# Sheet1.net
KiCad netlist of a schematic drawn in Altium Designer
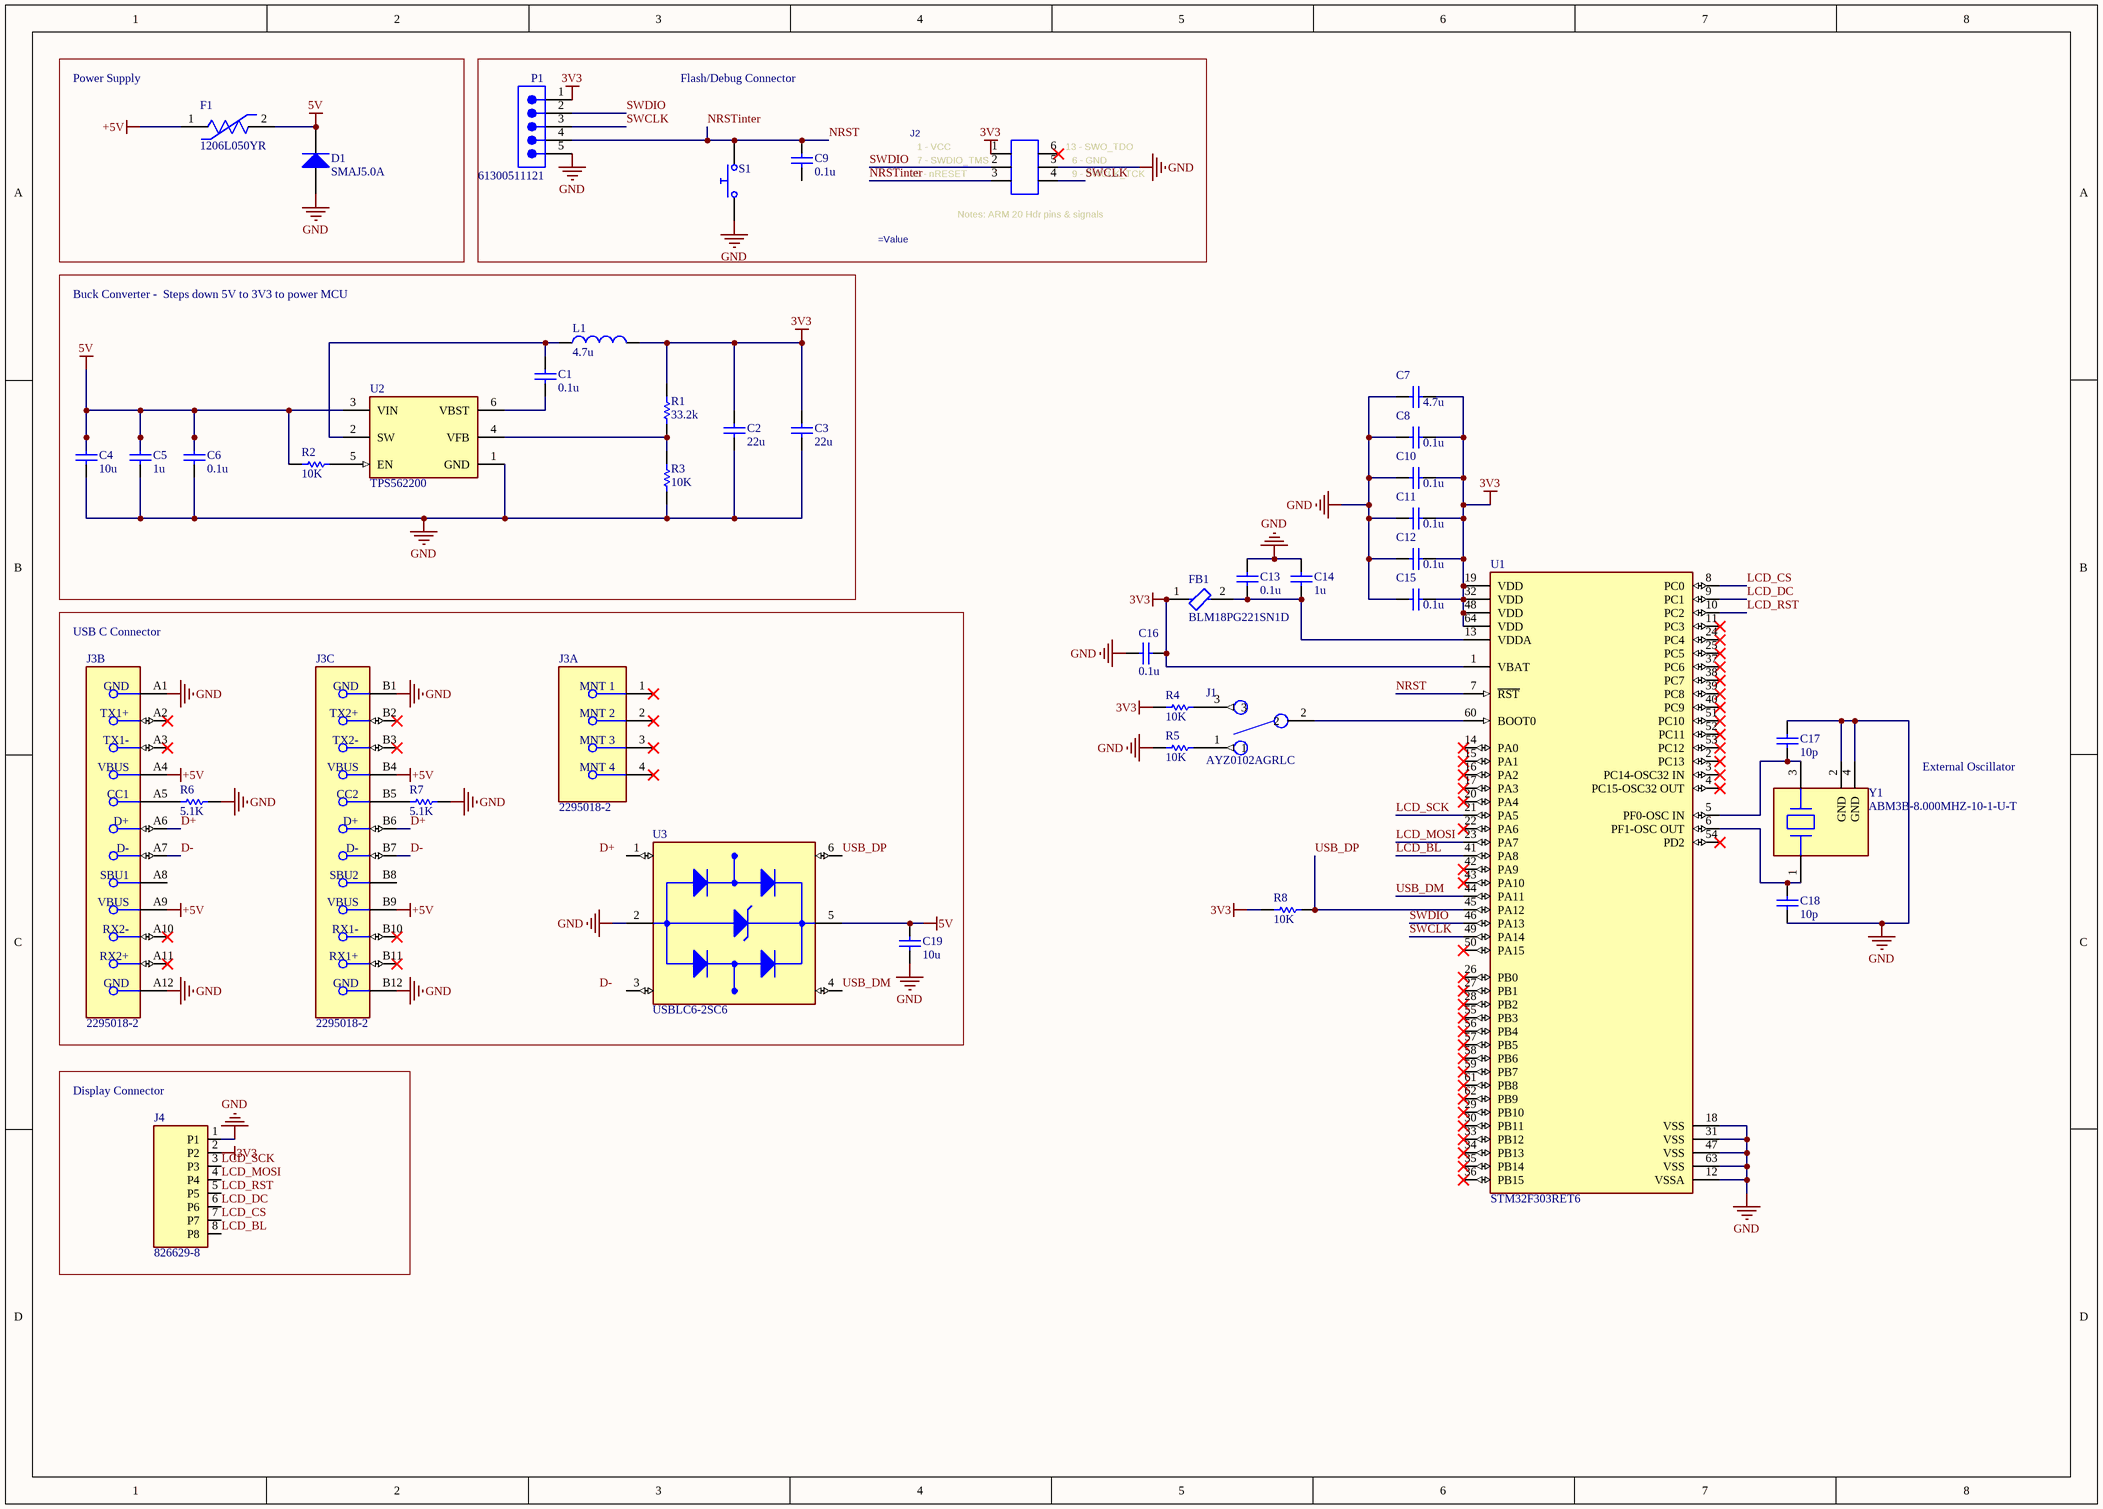
[diagram p0: Sheet1.SchDoc]

(export (version "E")
  (design (tool "Eeschema 10.0.6"))
  (components
    (comp (ref "C1")
      (value "0.1u")
      (description "Capacitor")
      (libsource (lib "Simulation Generic Components") (part "Capacitor"))
    )
    (comp (ref "C2")
      (value "22u")
      (description "Capacitor")
      (libsource (lib "Simulation Generic Components") (part "Capacitor"))
    )
    (comp (ref "C3")
      (value "22u")
      (description "Capacitor")
      (libsource (lib "Simulation Generic Components") (part "Capacitor"))
    )
    (comp (ref "C4")
      (value "10u")
      (description "Capacitor")
      (libsource (lib "Simulation Generic Components") (part "Capacitor"))
    )
    (comp (ref "C5")
      (value "1u")
      (description "Capacitor")
      (libsource (lib "Simulation Generic Components") (part "Capacitor"))
    )
    (comp (ref "C6")
      (value "0.1u")
      (description "Capacitor")
      (libsource (lib "Simulation Generic Components") (part "Capacitor"))
    )
    (comp (ref "C7")
      (value "4.7u")
      (description "Capacitor")
      (libsource (lib "Simulation Generic Components") (part "Capacitor"))
    )
    (comp (ref "C8")
      (value "0.1u")
      (description "Capacitor")
      (libsource (lib "Simulation Generic Components") (part "Capacitor"))
    )
    (comp (ref "C9")
      (value "0.1u")
      (description "Capacitor")
      (libsource (lib "Simulation Generic Components") (part "Capacitor"))
    )
    (comp (ref "C10")
      (value "0.1u")
      (description "Capacitor")
      (libsource (lib "Simulation Generic Components") (part "Capacitor"))
    )
    (comp (ref "C11")
      (value "0.1u")
      (description "Capacitor")
      (libsource (lib "Simulation Generic Components") (part "Capacitor"))
    )
    (comp (ref "C12")
      (value "0.1u")
      (description "Capacitor")
      (libsource (lib "Simulation Generic Components") (part "Capacitor"))
    )
    (comp (ref "C13")
      (value "0.1u")
      (description "Capacitor")
      (libsource (lib "Simulation Generic Components") (part "Capacitor"))
    )
    (comp (ref "C14")
      (value "1u")
      (description "Capacitor")
      (libsource (lib "Simulation Generic Components") (part "Capacitor"))
    )
    (comp (ref "C15")
      (value "0.1u")
      (description "Capacitor")
      (libsource (lib "Simulation Generic Components") (part "Capacitor"))
    )
    (comp (ref "C16")
      (value "0.1u")
      (description "Capacitor")
      (libsource (lib "Simulation Generic Components") (part "Capacitor"))
    )
    (comp (ref "C17")
      (value "10p")
      (description "Capacitor")
      (libsource (lib "Simulation Generic Components") (part "Capacitor"))
    )
    (comp (ref "C18")
      (value "10p")
      (description "Capacitor")
      (libsource (lib "Simulation Generic Components") (part "Capacitor"))
    )
    (comp (ref "C19")
      (value "10u")
      (description "Capacitor")
      (libsource (lib "Simulation Generic Components") (part "Capacitor"))
    )
    (comp (ref "D1")
      (value "SMAJ5.0A")
      (footprint "BOUR-SMA-2_V")
      (fields (field (name "MANUFACTURER") "Bourns"))
      (libsource (lib "Altium Content Vault") (part "D-AK-2"))
    )
    (comp (ref "F1")
      (value "1206L050YR")
      (footprint "FP-1206L050YR-MFG")
      (description "PTC RESET FUSE 6V 500MA 1206")
      (libsource (lib "Altium Content Vault") (part "fdf083d5f6389a9a1c4e51137f46658"))
    )
    (comp (ref "FB1")
      (value "BLM18PG221SN1D")
      (footprint "FP-BLM18-0_15-t0_8-IPC_B")
      (description "Chip Ferrite Bead, 0603, 220Ω @ 100MHz, 0.1Ω, 25%, 1.4A")
      (fields (field (name "TOLERANCE") "25%"))
      (libsource (lib "Altium Content Vault") (part "5f30dd21d616792df468990f7003faa"))
    )
    (comp (ref "J1")
      (value "AYZ0102AGRLC")
      (footprint "SW_AYZ0102AGRLC")
      (description "Slide Switch SPDT Surface Mount, Right Angle")
      (fields (field (name "MF") "C&K"))
      (libsource (lib "AYZ0102AGRLC") (part "AYZ0102AGRLC"))
    )
    (comp (ref "J2")
      (value "~")
      (footprint "TC2030-IDC")
      (description "HDR, TC2030, 6 Pin, Footprint only")
      (libsource (lib "TagConnect-20Apr2013") (part "HDR 6 TC2030-NL"))
    )
    (comp (ref "J3")
      (value "2295018-2")
      (footprint "FP-2295018-2-MFG")
      (description "CONN RCPT USB3.1 TYPEC 24POS SMD")
      (libsource (lib "Altium Content Vault") (part "679c62bc5b49f2b3fbc1f29b048fd31"))
    )
    (comp (ref "J4")
      (value "826629-8")
      (footprint "TE_826629-8")
      (description "Conn Unshrouded Header HDR 8 POS 2.54mm Solder ST Thru-Hole Automotive Box")
      (fields (field (name "MF") "TE Connectivity"))
      (libsource (lib "826629-8") (part "826629-8"))
    )
    (comp (ref "L1")
      (value "4.7u")
      (description "Inductor")
      (libsource (lib "Simulation Generic Components") (part "Inductor"))
    )
    (comp (ref "P1")
      (value "61300511121")
      (footprint "61300511121")
      (description "THT Vertical Pin Header WR-PHD, Pitch 2.54 mm, Single Row, 5 pins")
      (libsource (lib "Altium Content Vault") (part "Header_Male_1R_05P"))
    )
    (comp (ref "R1")
      (value "33.2k")
      (description "Resistor")
      (libsource (lib "Simulation Generic Components") (part "Resistor"))
    )
    (comp (ref "R2")
      (value "10K")
      (description "Resistor")
      (libsource (lib "Simulation Generic Components") (part "Resistor"))
    )
    (comp (ref "R3")
      (value "10K")
      (description "Resistor")
      (libsource (lib "Simulation Generic Components") (part "Resistor"))
    )
    (comp (ref "R4")
      (value "10K")
      (description "Resistor")
      (libsource (lib "Simulation Generic Components") (part "Resistor"))
    )
    (comp (ref "R5")
      (value "10K")
      (description "Resistor")
      (libsource (lib "Simulation Generic Components") (part "Resistor"))
    )
    (comp (ref "R6")
      (value "5.1K")
      (description "Resistor")
      (libsource (lib "Simulation Generic Components") (part "Resistor"))
    )
    (comp (ref "R7")
      (value "5.1K")
      (description "Resistor")
      (libsource (lib "Simulation Generic Components") (part "Resistor"))
    )
    (comp (ref "R8")
      (value "10K")
      (description "Resistor")
      (libsource (lib "Simulation Generic Components") (part "Resistor"))
    )
    (comp (ref "S1")
      (value "Push Button Normally Opened")
      (libsource (lib "Simulation Generic Components") (part "Push Button NO"))
    )
    (comp (ref "U1")
      (value "STM32F303RET6")
      (footprint "FP-LQFP64-5W-MFG")
      (description "IC MCU 32BIT 512KB FLASH 64LQFP")
      (fields
        (field (name "MANUFACTURER") "STMicroelectronics")
        (field (name "OCTOPART") "https://octopart.com/stm32f303ret6-stmicroelectronics-53115257")
      )
      (libsource (lib "Altium Content Vault") (part "7a78af9fccac3dafce8a4966595e415"))
    )
    (comp (ref "U2")
      (value "TPS562200")
      (footprint "FP-DDC0006A-MFG")
      (description "IC REG BUCK ADJ 2A TSOT23-6")
      (fields
        (field (name "MANUFACTURER PART NUMBER") "TPS562201DDCT")
        (field (name "OCTOPART") "https://octopart.com/tps562201ddct-texas+instruments-68059584")
      )
      (libsource (lib "Altium Content Vault") (part "06d79c7d29d628b4662ce6edb459819"))
    )
    (comp (ref "U3")
      (value "USBLC6-2SC6")
      (footprint "SOT95P280X145-6N")
      (description "17V Clamp 5A (8/20Âµs) Ipp Tvs Diode Surface Mount SOT-23-6")
      (fields (field (name "MF") "STMicroelectronics"))
      (libsource (lib "USBLC6-2SC6") (part "USBLC6-2SC6"))
    )
    (comp (ref "Y1")
      (value "ABM3B-8.000MHZ-10-1-U-T")
      (footprint "FP-ABM3B-MFG")
      (description "Crystal 8MHz ±10ppm 10pF SMD-4 5mm x 3.2mm")
      (libsource (lib "Altium Content Vault") (part "48e526d86b7f2615d98721063c72f49"))
    )
  )
  (nets
    (net (code "1") (name "+5V") (class "Default")
      (node (ref "F1") (pin "1") (pinfunction "1_1") (pintype "passive"))
      (node (ref "J3") (pin "A4") (pinfunction "VBUS_A4") (pintype "power_in"))
      (node (ref "J3") (pin "A9") (pinfunction "VBUS_A9") (pintype "power_in"))
      (node (ref "J3") (pin "B4") (pinfunction "VBUS_B4") (pintype "passive"))
      (node (ref "J3") (pin "B9") (pinfunction "VBUS_B9") (pintype "power_in"))
    )
    (net (code "2") (name "/D+") (class "Default")
      (node (ref "J3") (pin "A6") (pinfunction "D+_A6") (pintype "bidirectional"))
      (node (ref "J3") (pin "B6") (pinfunction "D+_B6") (pintype "bidirectional"))
    )
    (net (code "3") (name "/D-") (class "Default")
      (node (ref "J3") (pin "A7") (pinfunction "D-_A7") (pintype "bidirectional"))
      (node (ref "J3") (pin "B7") (pinfunction "D-_B7") (pintype "bidirectional"))
    )
    (net (code "4") (name "/LCD_BL") (class "Default")
      (node (ref "J4") (pin "8") (pinfunction "P8_8") (pintype "passive"))
      (node (ref "U1") (pin "41") (pinfunction "PA8_41") (pintype "bidirectional"))
    )
    (net (code "5") (name "/LCD_CS") (class "Default")
      (node (ref "J4") (pin "7") (pinfunction "P7_7") (pintype "passive"))
      (node (ref "U1") (pin "8") (pinfunction "PC0_8") (pintype "bidirectional"))
    )
    (net (code "6") (name "/LCD_DC") (class "Default")
      (node (ref "J4") (pin "6") (pinfunction "P6_6") (pintype "passive"))
      (node (ref "U1") (pin "9") (pinfunction "PC1_9") (pintype "bidirectional"))
    )
    (net (code "7") (name "/LCD_MOSI") (class "Default")
      (node (ref "J4") (pin "4") (pinfunction "P4_4") (pintype "passive"))
      (node (ref "U1") (pin "23") (pinfunction "PA7_23") (pintype "bidirectional"))
    )
    (net (code "8") (name "/LCD_RST") (class "Default")
      (node (ref "J4") (pin "5") (pinfunction "P5_5") (pintype "passive"))
      (node (ref "U1") (pin "10") (pinfunction "PC2_10") (pintype "bidirectional"))
    )
    (net (code "9") (name "/LCD_SCK") (class "Default")
      (node (ref "J4") (pin "3") (pinfunction "P3_3") (pintype "passive"))
      (node (ref "U1") (pin "21") (pinfunction "PA5_21") (pintype "bidirectional"))
    )
    (net (code "10") (name "/NRST") (class "Default")
      (node (ref "C9") (pin "2") (pinfunction "2_2") (pintype "passive"))
      (node (ref "J2") (pin "3") (pinfunction "3_3") (pintype "passive"))
      (node (ref "P1") (pin "4") (pinfunction "4_4") (pintype "passive"))
      (node (ref "S1") (pin "2") (pinfunction "2_2") (pintype "passive"))
      (node (ref "U1") (pin "7") (pinfunction "~{RST}_7") (pintype "input"))
    )
    (net (code "11") (name "/SWCLK") (class "Default")
      (node (ref "J2") (pin "4") (pinfunction "4_4") (pintype "passive"))
      (node (ref "P1") (pin "3") (pinfunction "3_3") (pintype "passive"))
      (node (ref "U1") (pin "49") (pinfunction "PA14_49") (pintype "bidirectional"))
    )
    (net (code "12") (name "/SWDIO") (class "Default")
      (node (ref "J2") (pin "2") (pinfunction "2_2") (pintype "passive"))
      (node (ref "P1") (pin "2") (pinfunction "2_2") (pintype "passive"))
      (node (ref "U1") (pin "46") (pinfunction "PA13_46") (pintype "bidirectional"))
    )
    (net (code "13") (name "/USB_DM") (class "Default")
      (node (ref "U1") (pin "44") (pinfunction "PA11_44") (pintype "bidirectional"))
      (node (ref "U3") (pin "4") (pinfunction "I/O2_OUT_4") (pintype "bidirectional"))
    )
    (net (code "14") (name "/USB_DP") (class "Default")
      (node (ref "R8") (pin "2") (pinfunction "2_2") (pintype "passive"))
      (node (ref "U1") (pin "45") (pinfunction "PA12_45") (pintype "bidirectional"))
      (node (ref "U3") (pin "6") (pinfunction "I/O1_OUT_6") (pintype "bidirectional"))
    )
    (net (code "15") (name "3V3") (class "Default")
      (node (ref "C10") (pin "1") (pinfunction "1_1") (pintype "passive"))
      (node (ref "C11") (pin "1") (pinfunction "1_1") (pintype "passive"))
      (node (ref "C12") (pin "1") (pinfunction "1_1") (pintype "passive"))
      (node (ref "C15") (pin "1") (pinfunction "1_1") (pintype "passive"))
      (node (ref "C16") (pin "2") (pinfunction "2_2") (pintype "passive"))
      (node (ref "C2") (pin "2") (pinfunction "2_2") (pintype "passive"))
      (node (ref "C3") (pin "2") (pinfunction "2_2") (pintype "passive"))
      (node (ref "C7") (pin "1") (pinfunction "1_1") (pintype "passive"))
      (node (ref "C8") (pin "1") (pinfunction "1_1") (pintype "passive"))
      (node (ref "FB1") (pin "1") (pinfunction "1_1") (pintype "passive"))
      (node (ref "J2") (pin "1") (pinfunction "1_1") (pintype "passive"))
      (node (ref "J4") (pin "2") (pinfunction "P2_2") (pintype "passive"))
      (node (ref "L1") (pin "2") (pinfunction "2_2") (pintype "passive"))
      (node (ref "P1") (pin "1") (pinfunction "1_1") (pintype "passive"))
      (node (ref "R1") (pin "1") (pinfunction "1_1") (pintype "passive"))
      (node (ref "R4") (pin "1") (pinfunction "1_1") (pintype "passive"))
      (node (ref "R8") (pin "1") (pinfunction "1_1") (pintype "passive"))
      (node (ref "U1") (pin "1") (pinfunction "VBAT_1") (pintype "power_in"))
      (node (ref "U1") (pin "19") (pinfunction "VDD_19") (pintype "power_in"))
      (node (ref "U1") (pin "32") (pinfunction "VDD_32") (pintype "power_in"))
      (node (ref "U1") (pin "48") (pinfunction "VDD_48") (pintype "power_in"))
      (node (ref "U1") (pin "64") (pinfunction "VDD_64") (pintype "power_in"))
    )
    (net (code "16") (name "5V") (class "Default")
      (node (ref "C19") (pin "2") (pinfunction "2_2") (pintype "passive"))
      (node (ref "C4") (pin "2") (pinfunction "2_2") (pintype "passive"))
      (node (ref "C5") (pin "2") (pinfunction "2_2") (pintype "passive"))
      (node (ref "C6") (pin "2") (pinfunction "2_2") (pintype "passive"))
      (node (ref "D1") (pin "2") (pinfunction "K_2") (pintype "passive"))
      (node (ref "F1") (pin "2") (pinfunction "2_2") (pintype "passive"))
      (node (ref "R2") (pin "2") (pinfunction "2_2") (pintype "passive"))
      (node (ref "U2") (pin "3") (pinfunction "VIN_3") (pintype "power_in"))
      (node (ref "U3") (pin "5") (pinfunction "VBUS_5") (pintype "power_in"))
    )
    (net (code "17") (name "GND") (class "Default")
      (node (ref "C10") (pin "2") (pinfunction "2_2") (pintype "passive"))
      (node (ref "C11") (pin "2") (pinfunction "2_2") (pintype "passive"))
      (node (ref "C12") (pin "2") (pinfunction "2_2") (pintype "passive"))
      (node (ref "C13") (pin "1") (pinfunction "1_1") (pintype "passive"))
      (node (ref "C14") (pin "2") (pinfunction "2_2") (pintype "passive"))
      (node (ref "C15") (pin "2") (pinfunction "2_2") (pintype "passive"))
      (node (ref "C16") (pin "1") (pinfunction "1_1") (pintype "passive"))
      (node (ref "C17") (pin "1") (pinfunction "1_1") (pintype "passive"))
      (node (ref "C18") (pin "2") (pinfunction "2_2") (pintype "passive"))
      (node (ref "C19") (pin "1") (pinfunction "1_1") (pintype "passive"))
      (node (ref "C2") (pin "1") (pinfunction "1_1") (pintype "passive"))
      (node (ref "C3") (pin "1") (pinfunction "1_1") (pintype "passive"))
      (node (ref "C4") (pin "1") (pinfunction "1_1") (pintype "passive"))
      (node (ref "C5") (pin "1") (pinfunction "1_1") (pintype "passive"))
      (node (ref "C6") (pin "1") (pinfunction "1_1") (pintype "passive"))
      (node (ref "C7") (pin "2") (pinfunction "2_2") (pintype "passive"))
      (node (ref "C8") (pin "2") (pinfunction "2_2") (pintype "passive"))
      (node (ref "D1") (pin "1") (pinfunction "A_1") (pintype "passive"))
      (node (ref "J2") (pin "5") (pinfunction "5_5") (pintype "passive"))
      (node (ref "J3") (pin "A1") (pinfunction "GND_A1") (pintype "power_in"))
      (node (ref "J3") (pin "A12") (pinfunction "GND_A12") (pintype "power_in"))
      (node (ref "J3") (pin "B1") (pinfunction "GND_B1") (pintype "power_in"))
      (node (ref "J3") (pin "B12") (pinfunction "GND_B12") (pintype "power_in"))
      (node (ref "J4") (pin "1") (pinfunction "P1_1") (pintype "passive"))
      (node (ref "P1") (pin "5") (pinfunction "5_5") (pintype "passive"))
      (node (ref "R3") (pin "2") (pinfunction "2_2") (pintype "passive"))
      (node (ref "R5") (pin "1") (pinfunction "1_1") (pintype "passive"))
      (node (ref "R6") (pin "1") (pinfunction "1_1") (pintype "passive"))
      (node (ref "R7") (pin "1") (pinfunction "1_1") (pintype "passive"))
      (node (ref "S1") (pin "1") (pinfunction "1_1") (pintype "passive"))
      (node (ref "U1") (pin "12") (pinfunction "VSSA_12") (pintype "power_in"))
      (node (ref "U1") (pin "18") (pinfunction "VSS_18") (pintype "power_in"))
      (node (ref "U1") (pin "31") (pinfunction "VSS_31") (pintype "power_in"))
      (node (ref "U1") (pin "47") (pinfunction "VSS_47") (pintype "power_in"))
      (node (ref "U1") (pin "63") (pinfunction "VSS_63") (pintype "power_in"))
      (node (ref "U2") (pin "1") (pinfunction "GND_1") (pintype "power_in"))
      (node (ref "U3") (pin "2") (pinfunction "GND_2") (pintype "power_in"))
      (node (ref "Y1") (pin "2") (pinfunction "GND_2") (pintype "power_in"))
      (node (ref "Y1") (pin "4") (pinfunction "GND_4") (pintype "power_in"))
    )
    (net (code "18") (name "Net-(J1-Pad1)") (class "Default")
      (node (ref "J1") (pin "1") (pinfunction "1_1") (pintype "output"))
      (node (ref "R5") (pin "2") (pinfunction "2_2") (pintype "passive"))
    )
    (net (code "19") (name "Net-(J1-Pad3)") (class "Default")
      (node (ref "J1") (pin "3") (pinfunction "3_3") (pintype "output"))
      (node (ref "R4") (pin "2") (pinfunction "2_2") (pintype "passive"))
    )
    (net (code "20") (name "Net-(J3B-CC1)") (class "Default")
      (node (ref "J3") (pin "A5") (pinfunction "CC1_A5") (pintype "passive"))
      (node (ref "R6") (pin "2") (pinfunction "2_2") (pintype "passive"))
    )
    (net (code "21") (name "Net-(J3C-CC2)") (class "Default")
      (node (ref "J3") (pin "B5") (pinfunction "CC2_B5") (pintype "passive"))
      (node (ref "R7") (pin "2") (pinfunction "2_2") (pintype "passive"))
    )
    (net (code "22") (name "Net-(U1-BOOT0)") (class "Default")
      (node (ref "J1") (pin "2") (pinfunction "2_2") (pintype "power_in"))
      (node (ref "U1") (pin "60") (pinfunction "BOOT0_60") (pintype "input"))
    )
    (net (code "23") (name "Net-(U1-PF0-OSC_IN)") (class "Default")
      (node (ref "C17") (pin "2") (pinfunction "2_2") (pintype "passive"))
      (node (ref "U1") (pin "5") (pinfunction "PF0-OSC_IN_5") (pintype "bidirectional"))
      (node (ref "Y1") (pin "3") (pinfunction "3_3") (pintype "passive"))
    )
    (net (code "24") (name "Net-(U1-PF1-OSC_OUT)") (class "Default")
      (node (ref "C18") (pin "1") (pinfunction "1_1") (pintype "passive"))
      (node (ref "U1") (pin "6") (pinfunction "PF1-OSC_OUT_6") (pintype "bidirectional"))
      (node (ref "Y1") (pin "1") (pinfunction "1_1") (pintype "passive"))
    )
    (net (code "25") (name "Net-(U1-VDDA)") (class "Default")
      (node (ref "C13") (pin "2") (pinfunction "2_2") (pintype "passive"))
      (node (ref "C14") (pin "1") (pinfunction "1_1") (pintype "passive"))
      (node (ref "FB1") (pin "2") (pinfunction "2_2") (pintype "passive"))
      (node (ref "U1") (pin "13") (pinfunction "VDDA_13") (pintype "power_in"))
    )
    (net (code "26") (name "Net-(U2-EN)") (class "Default")
      (node (ref "R2") (pin "1") (pinfunction "1_1") (pintype "passive"))
      (node (ref "U2") (pin "5") (pinfunction "EN_5") (pintype "input"))
    )
    (net (code "27") (name "Net-(U2-SW)") (class "Default")
      (node (ref "C1") (pin "2") (pinfunction "2_2") (pintype "passive"))
      (node (ref "L1") (pin "1") (pinfunction "1_1") (pintype "passive"))
      (node (ref "U2") (pin "2") (pinfunction "SW_2") (pintype "passive"))
    )
    (net (code "28") (name "Net-(U2-VBST)") (class "Default")
      (node (ref "C1") (pin "1") (pinfunction "1_1") (pintype "passive"))
      (node (ref "U2") (pin "6") (pinfunction "VBST_6") (pintype "power_in"))
    )
    (net (code "29") (name "Net-(U2-VFB)") (class "Default")
      (node (ref "R1") (pin "2") (pinfunction "2_2") (pintype "passive"))
      (node (ref "R3") (pin "1") (pinfunction "1_1") (pintype "passive"))
      (node (ref "U2") (pin "4") (pinfunction "VFB_4") (pintype "passive"))
    )
    (net (code "30") (name "unconnected-(C9-Pad1)") (class "Default")
      (node (ref "C9") (pin "1") (pinfunction "1_1") (pintype "passive"))
    )
    (net (code "31") (name "unconnected-(J2-Pad6)") (class "Default")
      (node (ref "J2") (pin "6") (pinfunction "6_6") (pintype "passive+no_connect"))
    )
    (net (code "32") (name "unconnected-(J3A-MNT_1-Pad1)") (class "Default")
      (node (ref "J3") (pin "1") (pinfunction "MNT_1_1") (pintype "passive+no_connect"))
    )
    (net (code "33") (name "unconnected-(J3A-MNT_2-Pad2)") (class "Default")
      (node (ref "J3") (pin "2") (pinfunction "MNT_2_2") (pintype "passive+no_connect"))
    )
    (net (code "34") (name "unconnected-(J3A-MNT_3-Pad3)") (class "Default")
      (node (ref "J3") (pin "3") (pinfunction "MNT_3_3") (pintype "passive+no_connect"))
    )
    (net (code "35") (name "unconnected-(J3A-MNT_4-Pad4)") (class "Default")
      (node (ref "J3") (pin "4") (pinfunction "MNT_4_4") (pintype "passive+no_connect"))
    )
    (net (code "36") (name "unconnected-(J3B-RX2+-PadA11)") (class "Default")
      (node (ref "J3") (pin "A11") (pinfunction "RX2+_A11") (pintype "bidirectional+no_connect"))
    )
    (net (code "37") (name "unconnected-(J3B-RX2--PadA10)") (class "Default")
      (node (ref "J3") (pin "A10") (pinfunction "RX2-_A10") (pintype "bidirectional+no_connect"))
    )
    (net (code "38") (name "unconnected-(J3B-SBU1-PadA8)") (class "Default")
      (node (ref "J3") (pin "A8") (pinfunction "SBU1_A8") (pintype "power_in"))
    )
    (net (code "39") (name "unconnected-(J3B-TX1+-PadA2)") (class "Default")
      (node (ref "J3") (pin "A2") (pinfunction "TX1+_A2") (pintype "bidirectional+no_connect"))
    )
    (net (code "40") (name "unconnected-(J3B-TX1--PadA3)") (class "Default")
      (node (ref "J3") (pin "A3") (pinfunction "TX1-_A3") (pintype "bidirectional+no_connect"))
    )
    (net (code "41") (name "unconnected-(J3C-RX1+-PadB11)") (class "Default")
      (node (ref "J3") (pin "B11") (pinfunction "RX1+_B11") (pintype "bidirectional+no_connect"))
    )
    (net (code "42") (name "unconnected-(J3C-RX1--PadB10)") (class "Default")
      (node (ref "J3") (pin "B10") (pinfunction "RX1-_B10") (pintype "bidirectional+no_connect"))
    )
    (net (code "43") (name "unconnected-(J3C-SBU2-PadB8)") (class "Default")
      (node (ref "J3") (pin "B8") (pinfunction "SBU2_B8") (pintype "passive"))
    )
    (net (code "44") (name "unconnected-(J3C-TX2+-PadB2)") (class "Default")
      (node (ref "J3") (pin "B2") (pinfunction "TX2+_B2") (pintype "bidirectional+no_connect"))
    )
    (net (code "45") (name "unconnected-(J3C-TX2--PadB3)") (class "Default")
      (node (ref "J3") (pin "B3") (pinfunction "TX2-_B3") (pintype "bidirectional+no_connect"))
    )
    (net (code "46") (name "unconnected-(U1-PA0-Pad14)") (class "Default")
      (node (ref "U1") (pin "14") (pinfunction "PA0_14") (pintype "bidirectional+no_connect"))
    )
    (net (code "47") (name "unconnected-(U1-PA1-Pad15)") (class "Default")
      (node (ref "U1") (pin "15") (pinfunction "PA1_15") (pintype "bidirectional+no_connect"))
    )
    (net (code "48") (name "unconnected-(U1-PA2-Pad16)") (class "Default")
      (node (ref "U1") (pin "16") (pinfunction "PA2_16") (pintype "bidirectional+no_connect"))
    )
    (net (code "49") (name "unconnected-(U1-PA3-Pad17)") (class "Default")
      (node (ref "U1") (pin "17") (pinfunction "PA3_17") (pintype "bidirectional+no_connect"))
    )
    (net (code "50") (name "unconnected-(U1-PA4-Pad20)") (class "Default")
      (node (ref "U1") (pin "20") (pinfunction "PA4_20") (pintype "bidirectional+no_connect"))
    )
    (net (code "51") (name "unconnected-(U1-PA6-Pad22)") (class "Default")
      (node (ref "U1") (pin "22") (pinfunction "PA6_22") (pintype "bidirectional+no_connect"))
    )
    (net (code "52") (name "unconnected-(U1-PA9-Pad42)") (class "Default")
      (node (ref "U1") (pin "42") (pinfunction "PA9_42") (pintype "bidirectional+no_connect"))
    )
    (net (code "53") (name "unconnected-(U1-PA10-Pad43)") (class "Default")
      (node (ref "U1") (pin "43") (pinfunction "PA10_43") (pintype "bidirectional+no_connect"))
    )
    (net (code "54") (name "unconnected-(U1-PA15-Pad50)") (class "Default")
      (node (ref "U1") (pin "50") (pinfunction "PA15_50") (pintype "bidirectional+no_connect"))
    )
    (net (code "55") (name "unconnected-(U1-PB0-Pad26)") (class "Default")
      (node (ref "U1") (pin "26") (pinfunction "PB0_26") (pintype "bidirectional+no_connect"))
    )
    (net (code "56") (name "unconnected-(U1-PB1-Pad27)") (class "Default")
      (node (ref "U1") (pin "27") (pinfunction "PB1_27") (pintype "bidirectional+no_connect"))
    )
    (net (code "57") (name "unconnected-(U1-PB2-Pad28)") (class "Default")
      (node (ref "U1") (pin "28") (pinfunction "PB2_28") (pintype "bidirectional+no_connect"))
    )
    (net (code "58") (name "unconnected-(U1-PB3-Pad55)") (class "Default")
      (node (ref "U1") (pin "55") (pinfunction "PB3_55") (pintype "bidirectional+no_connect"))
    )
    (net (code "59") (name "unconnected-(U1-PB4-Pad56)") (class "Default")
      (node (ref "U1") (pin "56") (pinfunction "PB4_56") (pintype "bidirectional+no_connect"))
    )
    (net (code "60") (name "unconnected-(U1-PB5-Pad57)") (class "Default")
      (node (ref "U1") (pin "57") (pinfunction "PB5_57") (pintype "bidirectional+no_connect"))
    )
    (net (code "61") (name "unconnected-(U1-PB6-Pad58)") (class "Default")
      (node (ref "U1") (pin "58") (pinfunction "PB6_58") (pintype "bidirectional+no_connect"))
    )
    (net (code "62") (name "unconnected-(U1-PB7-Pad59)") (class "Default")
      (node (ref "U1") (pin "59") (pinfunction "PB7_59") (pintype "bidirectional+no_connect"))
    )
    (net (code "63") (name "unconnected-(U1-PB8-Pad61)") (class "Default")
      (node (ref "U1") (pin "61") (pinfunction "PB8_61") (pintype "bidirectional+no_connect"))
    )
    (net (code "64") (name "unconnected-(U1-PB9-Pad62)") (class "Default")
      (node (ref "U1") (pin "62") (pinfunction "PB9_62") (pintype "bidirectional+no_connect"))
    )
    (net (code "65") (name "unconnected-(U1-PB10-Pad29)") (class "Default")
      (node (ref "U1") (pin "29") (pinfunction "PB10_29") (pintype "bidirectional+no_connect"))
    )
    (net (code "66") (name "unconnected-(U1-PB11-Pad30)") (class "Default")
      (node (ref "U1") (pin "30") (pinfunction "PB11_30") (pintype "bidirectional+no_connect"))
    )
    (net (code "67") (name "unconnected-(U1-PB12-Pad33)") (class "Default")
      (node (ref "U1") (pin "33") (pinfunction "PB12_33") (pintype "bidirectional+no_connect"))
    )
    (net (code "68") (name "unconnected-(U1-PB13-Pad34)") (class "Default")
      (node (ref "U1") (pin "34") (pinfunction "PB13_34") (pintype "bidirectional+no_connect"))
    )
    (net (code "69") (name "unconnected-(U1-PB14-Pad35)") (class "Default")
      (node (ref "U1") (pin "35") (pinfunction "PB14_35") (pintype "bidirectional+no_connect"))
    )
    (net (code "70") (name "unconnected-(U1-PB15-Pad36)") (class "Default")
      (node (ref "U1") (pin "36") (pinfunction "PB15_36") (pintype "bidirectional+no_connect"))
    )
    (net (code "71") (name "unconnected-(U1-PC3-Pad11)") (class "Default")
      (node (ref "U1") (pin "11") (pinfunction "PC3_11") (pintype "bidirectional+no_connect"))
    )
    (net (code "72") (name "unconnected-(U1-PC4-Pad24)") (class "Default")
      (node (ref "U1") (pin "24") (pinfunction "PC4_24") (pintype "bidirectional+no_connect"))
    )
    (net (code "73") (name "unconnected-(U1-PC5-Pad25)") (class "Default")
      (node (ref "U1") (pin "25") (pinfunction "PC5_25") (pintype "bidirectional+no_connect"))
    )
    (net (code "74") (name "unconnected-(U1-PC6-Pad37)") (class "Default")
      (node (ref "U1") (pin "37") (pinfunction "PC6_37") (pintype "bidirectional+no_connect"))
    )
    (net (code "75") (name "unconnected-(U1-PC7-Pad38)") (class "Default")
      (node (ref "U1") (pin "38") (pinfunction "PC7_38") (pintype "bidirectional+no_connect"))
    )
    (net (code "76") (name "unconnected-(U1-PC8-Pad39)") (class "Default")
      (node (ref "U1") (pin "39") (pinfunction "PC8_39") (pintype "bidirectional+no_connect"))
    )
    (net (code "77") (name "unconnected-(U1-PC9-Pad40)") (class "Default")
      (node (ref "U1") (pin "40") (pinfunction "PC9_40") (pintype "bidirectional+no_connect"))
    )
    (net (code "78") (name "unconnected-(U1-PC10-Pad51)") (class "Default")
      (node (ref "U1") (pin "51") (pinfunction "PC10_51") (pintype "bidirectional+no_connect"))
    )
    (net (code "79") (name "unconnected-(U1-PC11-Pad52)") (class "Default")
      (node (ref "U1") (pin "52") (pinfunction "PC11_52") (pintype "bidirectional+no_connect"))
    )
    (net (code "80") (name "unconnected-(U1-PC12-Pad53)") (class "Default")
      (node (ref "U1") (pin "53") (pinfunction "PC12_53") (pintype "bidirectional+no_connect"))
    )
    (net (code "81") (name "unconnected-(U1-PC13-Pad2)") (class "Default")
      (node (ref "U1") (pin "2") (pinfunction "PC13_2") (pintype "bidirectional+no_connect"))
    )
    (net (code "82") (name "unconnected-(U1-PC14-OSC32_IN-Pad3)") (class "Default")
      (node (ref "U1") (pin "3") (pinfunction "PC14-OSC32_IN_3") (pintype "bidirectional+no_connect"))
    )
    (net (code "83") (name "unconnected-(U1-PC15-OSC32_OUT-Pad4)") (class "Default")
      (node (ref "U1") (pin "4") (pinfunction "PC15-OSC32_OUT_4") (pintype "bidirectional+no_connect"))
    )
    (net (code "84") (name "unconnected-(U1-PD2-Pad54)") (class "Default")
      (node (ref "U1") (pin "54") (pinfunction "PD2_54") (pintype "bidirectional+no_connect"))
    )
    (net (code "85") (name "unconnected-(U3-I{slash}O1_IN-Pad1)") (class "Default")
      (node (ref "U3") (pin "1") (pinfunction "I/O1_IN_1") (pintype "bidirectional"))
    )
    (net (code "86") (name "unconnected-(U3-I{slash}O2_IN-Pad3)") (class "Default")
      (node (ref "U3") (pin "3") (pinfunction "I/O2_IN_3") (pintype "bidirectional"))
    )
  )
)
